# Steering_Converter_OG.net
KiCad netlist of a schematic drawn in Altium Designer
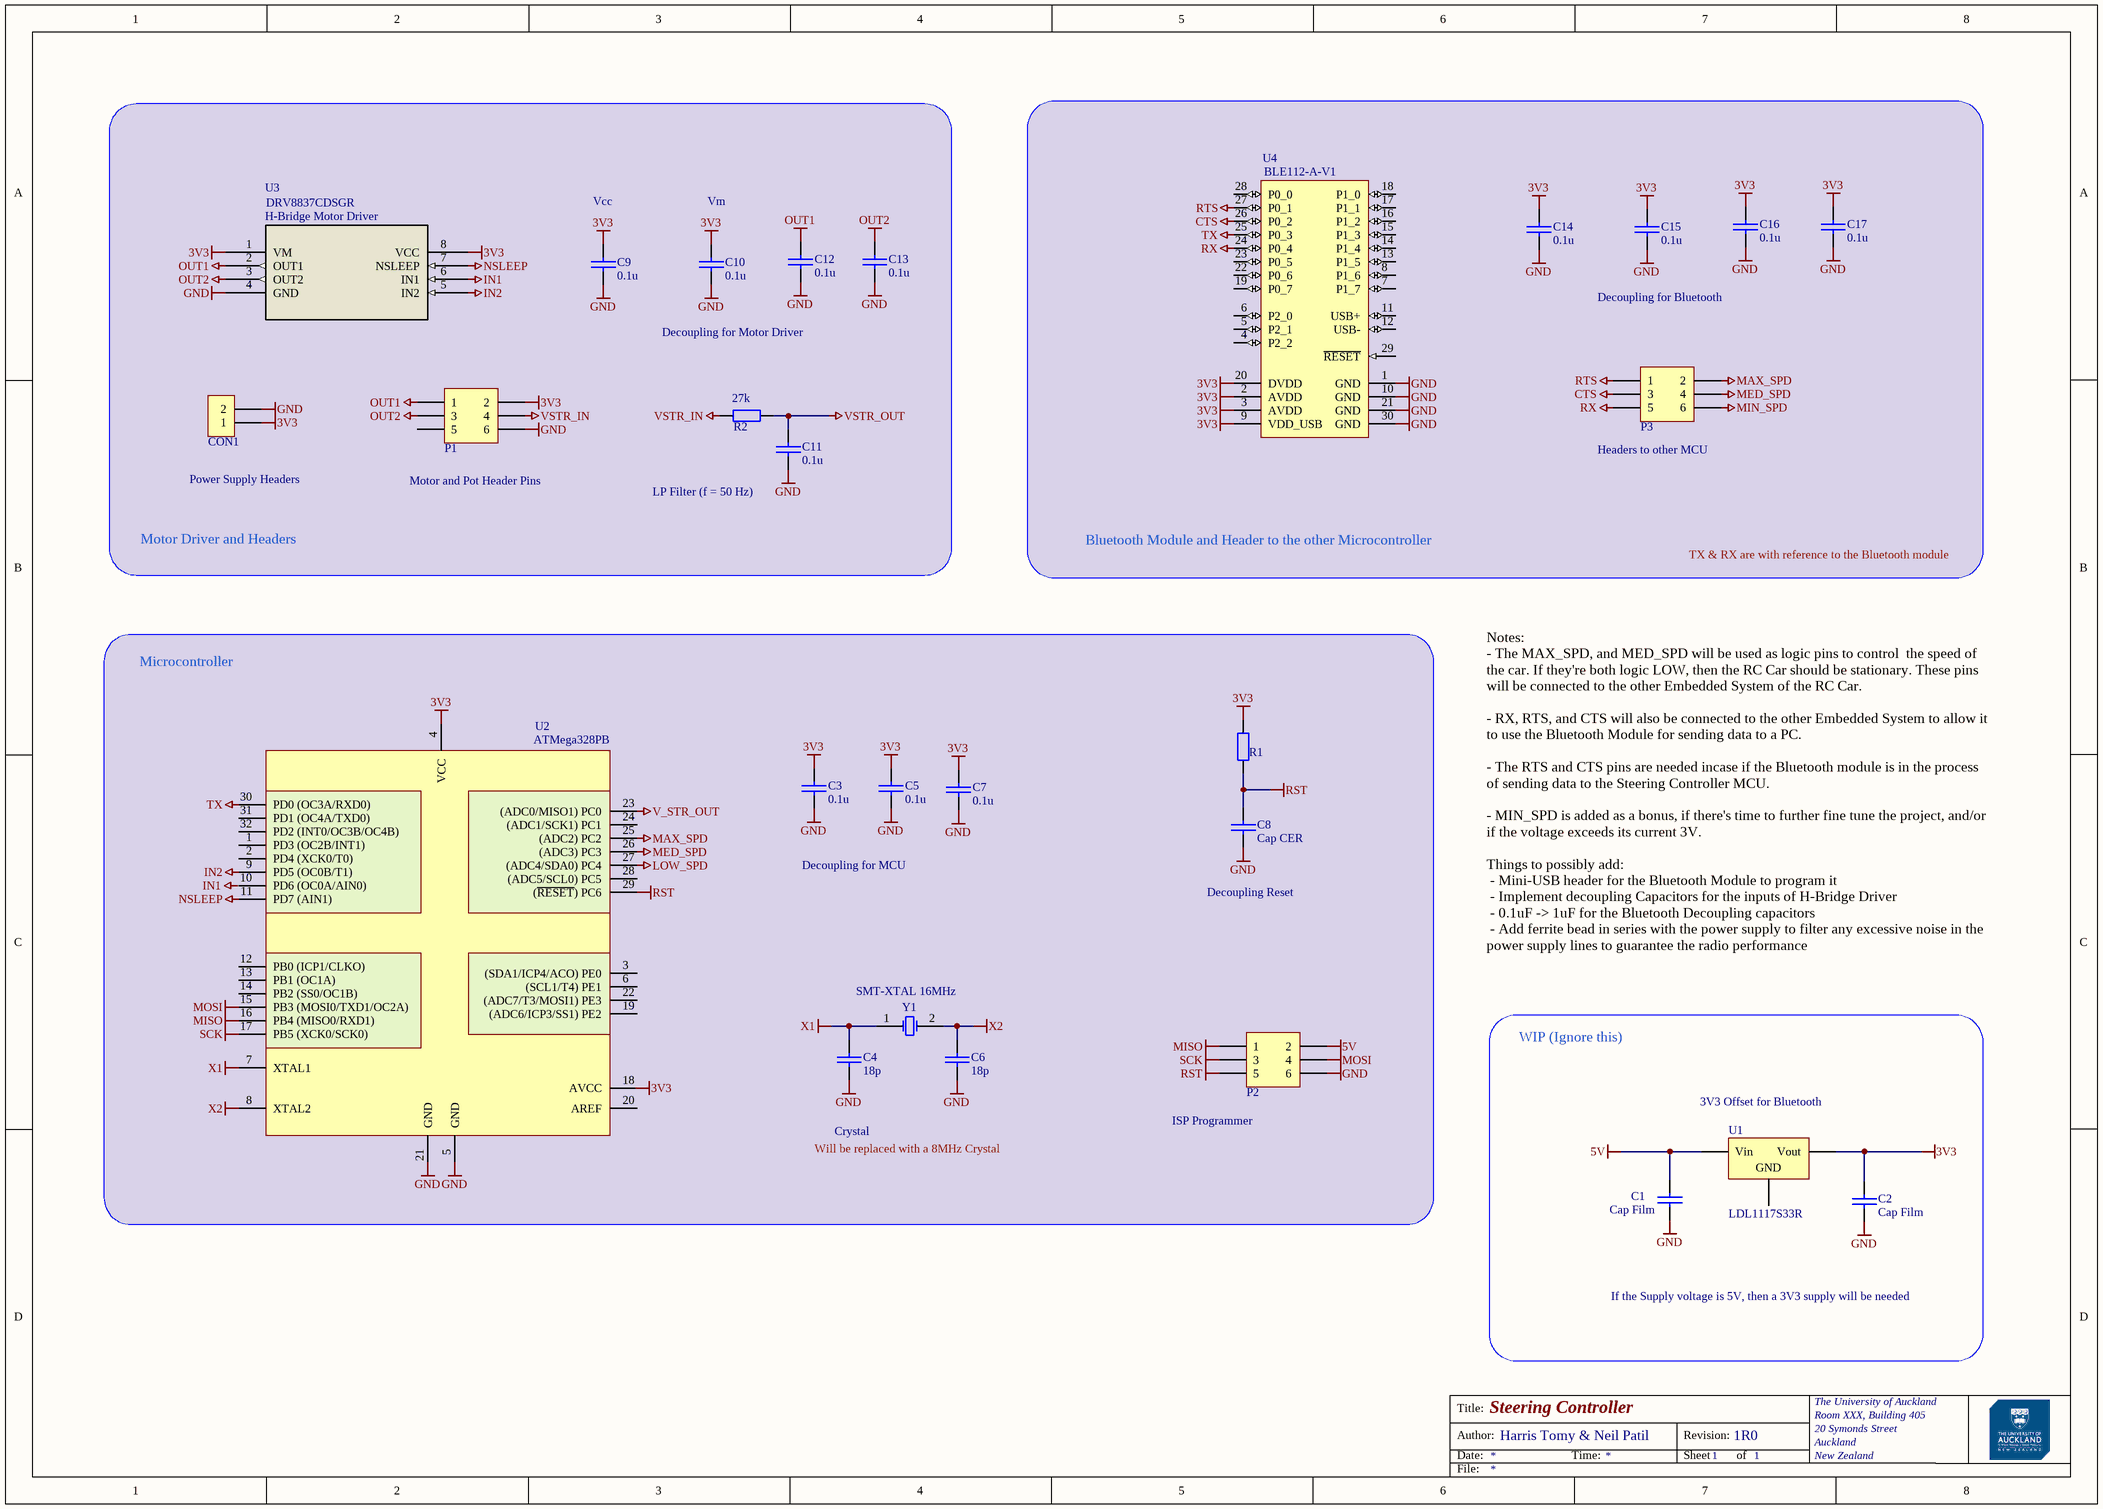
[diagram p0: Steering_Converter_OG.SchDoc]

(export (version "E")
  (design (tool "Eeschema 10.0.6"))
  (components
    (comp (ref "C1")
      (value "Cap Film")
      (footprint "LDECE4150KA0N00")
      (description "CAP FILM 1.5UF 10% 50VDC 2824")
      (fields (field (name "MPN") "LDECE4150KA0N00") (field (name "MANUFACTURER") "KEMET"))
      (libsource (lib "E209_Lib") (part "Cap Film SMD LDECE4150KA0N00"))
    )
    (comp (ref "C2")
      (value "Cap Film")
      (footprint "LDECE4150KA0N00")
      (description "CAP FILM 1.5UF 10% 50VDC 2824")
      (fields (field (name "MPN") "LDECE4150KA0N00") (field (name "MANUFACTURER") "KEMET"))
      (libsource (lib "E209_Lib") (part "Cap Film SMD LDECE4150KA0N00"))
    )
    (comp (ref "C3")
      (value "0.1u")
      (footprint "C1206")
      (description "CAP CER 0.1UF 100V C0G 1206")
      (fields (field (name "MPN") "C3216C0G2A104J160AC") (field (name "MANUFACTURER") "TDK Corporation"))
      (libsource (lib "E209_Lib") (part "Cap CER Decoup C3216C0G2A104J160AC"))
    )
    (comp (ref "C4")
      (value "18p")
      (footprint "C1206")
      (description "CAP CER 0.1UF 100V C0G 1206")
      (fields (field (name "MPN") "C3216C0G2A104J160AC") (field (name "MANUFACTURER") "TDK Corporation"))
      (libsource (lib "E209_Lib") (part "Cap CER Decoup C3216C0G2A104J160AC"))
    )
    (comp (ref "C5")
      (value "0.1u")
      (footprint "C1206")
      (description "CAP CER 0.1UF 100V C0G 1206")
      (fields (field (name "MPN") "C3216C0G2A104J160AC") (field (name "MANUFACTURER") "TDK Corporation"))
      (libsource (lib "E209_Lib") (part "Cap CER Decoup C3216C0G2A104J160AC"))
    )
    (comp (ref "C6")
      (value "18p")
      (footprint "C1206")
      (description "CAP CER 0.1UF 100V C0G 1206")
      (fields (field (name "MPN") "C3216C0G2A104J160AC") (field (name "MANUFACTURER") "TDK Corporation"))
      (libsource (lib "E209_Lib") (part "Cap CER Decoup C3216C0G2A104J160AC"))
    )
    (comp (ref "C7")
      (value "0.1u")
      (footprint "C1206")
      (description "CAP CER 0.1UF 100V C0G 1206")
      (fields (field (name "MPN") "C3216C0G2A104J160AC") (field (name "MANUFACTURER") "TDK Corporation"))
      (libsource (lib "E209_Lib") (part "Cap CER Decoup C3216C0G2A104J160AC"))
    )
    (comp (ref "C8")
      (value "Cap CER")
      (footprint "C1206")
      (description "CAP CER 0.1UF 100V C0G 1206")
      (fields (field (name "MPN") "C3216C0G2A104J160AC") (field (name "MANUFACTURER") "TDK Corporation"))
      (libsource (lib "E209_Lib") (part "Cap CER Decoup C3216C0G2A104J160AC"))
    )
    (comp (ref "C9")
      (value "0.1u")
      (footprint "C1206")
      (description "CAP CER 0.1UF 100V C0G 1206")
      (fields (field (name "MPN") "C3216C0G2A104J160AC") (field (name "MANUFACTURER") "TDK Corporation"))
      (libsource (lib "E209_Lib") (part "Cap CER Decoup C3216C0G2A104J160AC"))
    )
    (comp (ref "C10")
      (value "0.1u")
      (footprint "C1206")
      (description "CAP CER 0.1UF 100V C0G 1206")
      (fields (field (name "MPN") "C3216C0G2A104J160AC") (field (name "MANUFACTURER") "TDK Corporation"))
      (libsource (lib "E209_Lib") (part "Cap CER Decoup C3216C0G2A104J160AC"))
    )
    (comp (ref "C11")
      (value "0.1u")
      (footprint "C1206")
      (description "CAP CER 0.1UF 100V C0G 1206")
      (fields (field (name "MPN") "C3216C0G2A104J160AC") (field (name "MANUFACTURER") "TDK Corporation"))
      (libsource (lib "E209_Lib") (part "Cap CER Decoup C3216C0G2A104J160AC"))
    )
    (comp (ref "C12")
      (value "0.1u")
      (footprint "C1206")
      (description "CAP CER 0.1UF 100V C0G 1206")
      (fields (field (name "MPN") "C3216C0G2A104J160AC") (field (name "MANUFACTURER") "TDK Corporation"))
      (libsource (lib "E209_Lib") (part "Cap CER Decoup C3216C0G2A104J160AC"))
    )
    (comp (ref "C13")
      (value "0.1u")
      (footprint "C1206")
      (description "CAP CER 0.1UF 100V C0G 1206")
      (fields (field (name "MPN") "C3216C0G2A104J160AC") (field (name "MANUFACTURER") "TDK Corporation"))
      (libsource (lib "E209_Lib") (part "Cap CER Decoup C3216C0G2A104J160AC"))
    )
    (comp (ref "C14")
      (value "0.1u")
      (footprint "C1206")
      (description "CAP CER 0.1UF 100V C0G 1206")
      (fields (field (name "MPN") "C3216C0G2A104J160AC") (field (name "MANUFACTURER") "TDK Corporation"))
      (libsource (lib "E209_Lib") (part "Cap CER Decoup C3216C0G2A104J160AC"))
    )
    (comp (ref "C15")
      (value "0.1u")
      (footprint "C1206")
      (description "CAP CER 0.1UF 100V C0G 1206")
      (fields (field (name "MPN") "C3216C0G2A104J160AC") (field (name "MANUFACTURER") "TDK Corporation"))
      (libsource (lib "E209_Lib") (part "Cap CER Decoup C3216C0G2A104J160AC"))
    )
    (comp (ref "C16")
      (value "0.1u")
      (footprint "C1206")
      (description "CAP CER 0.1UF 100V C0G 1206")
      (fields (field (name "MPN") "C3216C0G2A104J160AC") (field (name "MANUFACTURER") "TDK Corporation"))
      (libsource (lib "E209_Lib") (part "Cap CER Decoup C3216C0G2A104J160AC"))
    )
    (comp (ref "C17")
      (value "0.1u")
      (footprint "C1206")
      (description "CAP CER 0.1UF 100V C0G 1206")
      (fields (field (name "MPN") "C3216C0G2A104J160AC") (field (name "MANUFACTURER") "TDK Corporation"))
      (libsource (lib "E209_Lib") (part "Cap CER Decoup C3216C0G2A104J160AC"))
    )
    (comp (ref "CON1")
      (value "Header 2X1")
      (footprint "HDR2X1_2P54")
      (libsource (lib "CommonDevices_V1") (part "HDR2X1"))
    )
    (comp (ref "P1")
      (value "HDR3X2")
      (footprint "HDR2X3_2P54")
      (description "Header, 3-Pin, Dual row")
      (libsource (lib "CommonDevices_V1") (part "HDR3X2"))
    )
    (comp (ref "P2")
      (value "HDR3X2")
      (footprint "HDR2X3_2P54")
      (description "Header, 3-Pin, Dual row")
      (libsource (lib "CommonDevices_V1") (part "HDR3X2"))
    )
    (comp (ref "P3")
      (value "HDR3X2")
      (footprint "HDR2X3_2P54")
      (description "Header, 3-Pin, Dual row")
      (libsource (lib "CommonDevices_V1") (part "HDR3X2"))
    )
    (comp (ref "R1")
      (value "Resistor 1206")
      (footprint "R1206")
      (description "RES1206")
      (fields (field (name "MPN") "?"))
      (libsource (lib "E209_Lib") (part "RES1206"))
    )
    (comp (ref "R2")
      (value "Resistor 0805")
      (footprint "R0805")
      (description "RES0805")
      (fields (field (name "MPN") "?"))
      (libsource (lib "E209_Lib") (part "RES0805"))
    )
    (comp (ref "U1")
      (value "LDL1117S33R")
      (footprint "SOT223L")
      (description "IC REG LINEAR 3.3V 1.2A SOT223")
      (fields (field (name "MANUFACTURER") "STMicroelectronics"))
      (libsource (lib "E209_Lib") (part "LDO LDL1117S33R"))
    )
    (comp (ref "U2")
      (value "ATMega328PB")
      (footprint "TQFP32")
      (description "IC MCU 8BIT 32KB FLASH 32TQFP")
      (libsource (lib "CommonDevices_V1") (part "ATMega328PB"))
    )
    (comp (ref "U3")
      (value "DRV8837CDSGR")
      (footprint "DSG8_P9X1P6_TEX")
      (description "No Description Available")
      (fields (field (name "COPYRIGHT") "Copyright (C) 2018 Accelerated Designs. All rights reserved"))
      (libsource (lib "H-Bridge_Driver_DRV8837C") (part "DRV8837CDSGR"))
    )
    (comp (ref "U4")
      (value "BLE112-A-V1")
      (footprint "BLUE-BLE112-A-V1_V")
      (libsource (lib "Integrated_Library1") (part "BLE112-A-V1"))
    )
    (comp (ref "Y1")
      (value "SMT-XTAL 16MHz")
      (footprint "HC49-US")
      (description "9C-16.000MAAJ-T crystal 16.0000MHZ 18PF SMD")
      (fields
        (field (name "MANUFACTURER") "TXC CORPORATION")
        (field (name "MANUFACTURER PART NUMBER") "9C-16.000MAAJ-T")
      )
      (libsource (lib "EE209_Library") (part "TXC9C-16_XTAL_SMT"))
    )
  )
  (nets
    (net (code "1") (name "3V3") (class "Default")
      (node (ref "C10") (pin "2") (pinfunction "2_2") (pintype "passive"))
      (node (ref "C14") (pin "2") (pinfunction "2_2") (pintype "passive"))
      (node (ref "C15") (pin "2") (pinfunction "2_2") (pintype "passive"))
      (node (ref "C16") (pin "2") (pinfunction "2_2") (pintype "passive"))
      (node (ref "C17") (pin "2") (pinfunction "2_2") (pintype "passive"))
      (node (ref "C2") (pin "2") (pinfunction "2_2") (pintype "passive"))
      (node (ref "C3") (pin "2") (pinfunction "2_2") (pintype "passive"))
      (node (ref "C5") (pin "2") (pinfunction "2_2") (pintype "passive"))
      (node (ref "C7") (pin "2") (pinfunction "2_2") (pintype "passive"))
      (node (ref "C9") (pin "2") (pinfunction "2_2") (pintype "passive"))
      (node (ref "CON1") (pin "1") (pinfunction "1_1") (pintype "passive"))
      (node (ref "P1") (pin "2") (pinfunction "2_2") (pintype "passive"))
      (node (ref "R1") (pin "1") (pinfunction "1_1") (pintype "passive"))
      (node (ref "U1") (pin "2") (pinfunction "Vout_2") (pintype "passive"))
      (node (ref "U2") (pin "4") (pinfunction "VCC_4") (pintype "passive"))
      (node (ref "U3") (pin "1") (pinfunction "VM_1") (pintype "power_in"))
      (node (ref "U3") (pin "8") (pinfunction "VCC_8") (pintype "power_in"))
      (node (ref "U4") (pin "2") (pinfunction "AVDD_2") (pintype "power_in"))
      (node (ref "U4") (pin "20") (pinfunction "DVDD_20") (pintype "power_in"))
      (node (ref "U4") (pin "3") (pinfunction "AVDD_3") (pintype "power_in"))
      (node (ref "U4") (pin "9") (pinfunction "VDD_USB_9") (pintype "power_in"))
    )
    (net (code "2") (name "5V") (class "Default")
      (node (ref "C1") (pin "2") (pinfunction "2_2") (pintype "passive"))
      (node (ref "P2") (pin "2") (pinfunction "2_2") (pintype "passive"))
      (node (ref "U1") (pin "3") (pinfunction "Vin_3") (pintype "passive"))
    )
    (net (code "3") (name "CTS") (class "Default")
      (node (ref "P3") (pin "3") (pinfunction "3_3") (pintype "passive"))
      (node (ref "U4") (pin "26") (pinfunction "P0_2_26") (pintype "bidirectional"))
    )
    (net (code "4") (name "GND") (class "Default")
      (node (ref "C1") (pin "1") (pinfunction "1_1") (pintype "passive"))
      (node (ref "C10") (pin "1") (pinfunction "1_1") (pintype "passive"))
      (node (ref "C11") (pin "1") (pinfunction "1_1") (pintype "passive"))
      (node (ref "C12") (pin "1") (pinfunction "1_1") (pintype "passive"))
      (node (ref "C13") (pin "1") (pinfunction "1_1") (pintype "passive"))
      (node (ref "C14") (pin "1") (pinfunction "1_1") (pintype "passive"))
      (node (ref "C15") (pin "1") (pinfunction "1_1") (pintype "passive"))
      (node (ref "C16") (pin "1") (pinfunction "1_1") (pintype "passive"))
      (node (ref "C17") (pin "1") (pinfunction "1_1") (pintype "passive"))
      (node (ref "C2") (pin "1") (pinfunction "1_1") (pintype "passive"))
      (node (ref "C3") (pin "1") (pinfunction "1_1") (pintype "passive"))
      (node (ref "C4") (pin "1") (pinfunction "1_1") (pintype "passive"))
      (node (ref "C5") (pin "1") (pinfunction "1_1") (pintype "passive"))
      (node (ref "C6") (pin "1") (pinfunction "1_1") (pintype "passive"))
      (node (ref "C7") (pin "1") (pinfunction "1_1") (pintype "passive"))
      (node (ref "C8") (pin "1") (pinfunction "1_1") (pintype "passive"))
      (node (ref "C9") (pin "1") (pinfunction "1_1") (pintype "passive"))
      (node (ref "CON1") (pin "2") (pinfunction "2_2") (pintype "passive"))
      (node (ref "P1") (pin "6") (pinfunction "6_6") (pintype "passive"))
      (node (ref "P2") (pin "6") (pinfunction "6_6") (pintype "passive"))
      (node (ref "U2") (pin "21") (pinfunction "GND_21") (pintype "passive"))
      (node (ref "U2") (pin "5") (pinfunction "GND_5") (pintype "passive"))
      (node (ref "U3") (pin "4") (pinfunction "GND_4") (pintype "power_in"))
      (node (ref "U4") (pin "1") (pinfunction "GND_1") (pintype "power_in"))
      (node (ref "U4") (pin "10") (pinfunction "GND_10") (pintype "power_in"))
      (node (ref "U4") (pin "21") (pinfunction "GND_21") (pintype "power_in"))
      (node (ref "U4") (pin "30") (pinfunction "GND_30") (pintype "power_in"))
    )
    (net (code "5") (name "IN1") (class "Default")
      (node (ref "U3") (pin "6") (pinfunction "IN1_6") (pintype "input"))
    )
    (net (code "6") (name "IN2") (class "Default")
      (node (ref "U2") (pin "9") (pinfunction "PD5_(OC0B/T1)_9") (pintype "passive"))
      (node (ref "U3") (pin "5") (pinfunction "IN2_5") (pintype "input"))
    )
    (net (code "7") (name "LOW_SPD") (class "Default")
      (node (ref "U2") (pin "27") (pinfunction "(ADC4/SDA0)_PC4_27") (pintype "passive"))
    )
    (net (code "8") (name "MAX_SPD") (class "Default")
      (node (ref "P3") (pin "2") (pinfunction "2_2") (pintype "passive"))
      (node (ref "U2") (pin "25") (pinfunction "(ADC2)_PC2_25") (pintype "passive"))
    )
    (net (code "9") (name "MED_SPD") (class "Default")
      (node (ref "P3") (pin "4") (pinfunction "4_4") (pintype "passive"))
      (node (ref "U2") (pin "26") (pinfunction "(ADC3)_PC3_26") (pintype "passive"))
    )
    (net (code "10") (name "MIN_SPD") (class "Default")
      (node (ref "P3") (pin "6") (pinfunction "6_6") (pintype "passive"))
    )
    (net (code "11") (name "MISO") (class "Default")
      (node (ref "P2") (pin "1") (pinfunction "1_1") (pintype "passive"))
      (node (ref "U2") (pin "16") (pinfunction "PB4_(MISO0/RXD1)_16") (pintype "passive"))
    )
    (net (code "12") (name "MOSI") (class "Default")
      (node (ref "P2") (pin "4") (pinfunction "4_4") (pintype "passive"))
      (node (ref "U2") (pin "15") (pinfunction "PB3_(MOSI0/TXD1/OC2A)_15") (pintype "passive"))
    )
    (net (code "13") (name "NSLEEP") (class "Default")
      (node (ref "U2") (pin "11") (pinfunction "PD7_(AIN1)_11") (pintype "passive"))
      (node (ref "U3") (pin "7") (pinfunction "NSLEEP_7") (pintype "input"))
    )
    (net (code "14") (name "OUT1") (class "Default")
      (node (ref "C12") (pin "2") (pinfunction "2_2") (pintype "passive"))
      (node (ref "P1") (pin "1") (pinfunction "1_1") (pintype "passive"))
      (node (ref "U3") (pin "2") (pinfunction "OUT1_2") (pintype "output"))
    )
    (net (code "15") (name "OUT2") (class "Default")
      (node (ref "C13") (pin "2") (pinfunction "2_2") (pintype "passive"))
      (node (ref "P1") (pin "3") (pinfunction "3_3") (pintype "passive"))
      (node (ref "U3") (pin "3") (pinfunction "OUT2_3") (pintype "output"))
    )
    (net (code "16") (name "RST") (class "Default")
      (node (ref "C8") (pin "2") (pinfunction "2_2") (pintype "passive"))
      (node (ref "P2") (pin "5") (pinfunction "5_5") (pintype "passive"))
      (node (ref "R1") (pin "2") (pinfunction "2_2") (pintype "passive"))
      (node (ref "U2") (pin "29") (pinfunction "(~{RESET})_PC6_29") (pintype "passive"))
    )
    (net (code "17") (name "RTS") (class "Default")
      (node (ref "P3") (pin "1") (pinfunction "1_1") (pintype "passive"))
      (node (ref "U4") (pin "27") (pinfunction "P0_1_27") (pintype "bidirectional"))
    )
    (net (code "18") (name "RX") (class "Default")
      (node (ref "P3") (pin "5") (pinfunction "5_5") (pintype "passive"))
      (node (ref "U4") (pin "24") (pinfunction "P0_4_24") (pintype "bidirectional"))
    )
    (net (code "19") (name "SCK") (class "Default")
      (node (ref "P2") (pin "3") (pinfunction "3_3") (pintype "passive"))
      (node (ref "U2") (pin "17") (pinfunction "PB5_(XCK0/SCK0)_17") (pintype "passive"))
    )
    (net (code "20") (name "TX") (class "Default")
      (node (ref "U2") (pin "30") (pinfunction "PD0_(OC3A/RXD0)_30") (pintype "passive"))
      (node (ref "U4") (pin "25") (pinfunction "P0_3_25") (pintype "bidirectional"))
    )
    (net (code "21") (name "VSTR_IN") (class "Default")
      (node (ref "P1") (pin "4") (pinfunction "4_4") (pintype "passive"))
      (node (ref "R2") (pin "1") (pinfunction "1_1") (pintype "passive"))
    )
    (net (code "22") (name "VSTR_OUT") (class "Default")
      (node (ref "C11") (pin "2") (pinfunction "2_2") (pintype "passive"))
      (node (ref "R2") (pin "2") (pinfunction "2_2") (pintype "passive"))
    )
    (net (code "23") (name "V_STR_OUT") (class "Default")
      (node (ref "U2") (pin "23") (pinfunction "(ADC0/MISO1)_PC0_23") (pintype "passive"))
    )
    (net (code "24") (name "X1") (class "Default")
      (node (ref "C4") (pin "2") (pinfunction "2_2") (pintype "passive"))
      (node (ref "U2") (pin "7") (pinfunction "XTAL1_7") (pintype "passive"))
      (node (ref "Y1") (pin "1") (pinfunction "OSC1_1") (pintype "passive"))
    )
    (net (code "25") (name "X2") (class "Default")
      (node (ref "C6") (pin "2") (pinfunction "2_2") (pintype "passive"))
      (node (ref "U2") (pin "8") (pinfunction "XTAL2_8") (pintype "passive"))
      (node (ref "Y1") (pin "2") (pinfunction "OSC2_2") (pintype "passive"))
    )
    (net (code "26") (name "unconnected-(P1-Pad5)") (class "Default")
      (node (ref "P1") (pin "5") (pinfunction "5_5") (pintype "passive"))
    )
    (net (code "27") (name "unconnected-(U1-GND-Pad1)") (class "Default")
      (node (ref "U1") (pin "1") (pinfunction "GND_1") (pintype "passive"))
    )
    (net (code "28") (name "unconnected-(U2-(ADC1{slash}SCK1)_PC1-Pad24)") (class "Default")
      (node (ref "U2") (pin "24") (pinfunction "(ADC1/SCK1)_PC1_24") (pintype "passive"))
    )
    (net (code "29") (name "unconnected-(U2-(ADC5{slash}SCL0)_PC5-Pad28)") (class "Default")
      (node (ref "U2") (pin "28") (pinfunction "(ADC5/SCL0)_PC5_28") (pintype "passive"))
    )
    (net (code "30") (name "unconnected-(U2-(ADC6{slash}ICP3{slash}SS1)_PE2-Pad19)") (class "Default")
      (node (ref "U2") (pin "19") (pinfunction "(ADC6/ICP3/SS1)_PE2_19") (pintype "passive"))
    )
    (net (code "31") (name "unconnected-(U2-(ADC7{slash}T3{slash}MOSI1)_PE3-Pad22)") (class "Default")
      (node (ref "U2") (pin "22") (pinfunction "(ADC7/T3/MOSI1)_PE3_22") (pintype "passive"))
    )
    (net (code "32") (name "unconnected-(U2-(SCL1{slash}T4)_PE1-Pad6)") (class "Default")
      (node (ref "U2") (pin "6") (pinfunction "(SCL1/T4)_PE1_6") (pintype "passive"))
    )
    (net (code "33") (name "unconnected-(U2-(SDA1{slash}ICP4{slash}ACO)_PE0-Pad3)") (class "Default")
      (node (ref "U2") (pin "3") (pinfunction "(SDA1/ICP4/ACO)_PE0_3") (pintype "passive"))
    )
    (net (code "34") (name "unconnected-(U2-AREF-Pad20)") (class "Default")
      (node (ref "U2") (pin "20") (pinfunction "AREF_20") (pintype "passive"))
    )
    (net (code "35") (name "unconnected-(U2-AVCC-Pad18)") (class "Default")
      (node (ref "U2") (pin "18") (pinfunction "AVCC_18") (pintype "passive"))
    )
    (net (code "36") (name "unconnected-(U2-PB0_(ICP1{slash}CLKO)-Pad12)") (class "Default")
      (node (ref "U2") (pin "12") (pinfunction "PB0_(ICP1/CLKO)_12") (pintype "passive"))
    )
    (net (code "37") (name "unconnected-(U2-PB1_(OC1A)-Pad13)") (class "Default")
      (node (ref "U2") (pin "13") (pinfunction "PB1_(OC1A)_13") (pintype "passive"))
    )
    (net (code "38") (name "unconnected-(U2-PB2_(SS0{slash}OC1B)-Pad14)") (class "Default")
      (node (ref "U2") (pin "14") (pinfunction "PB2_(SS0/OC1B)_14") (pintype "passive"))
    )
    (net (code "39") (name "unconnected-(U2-PD1_(OC4A{slash}TXD0)-Pad31)") (class "Default")
      (node (ref "U2") (pin "31") (pinfunction "PD1_(OC4A/TXD0)_31") (pintype "passive"))
    )
    (net (code "40") (name "unconnected-(U2-PD2_(INT0{slash}OC3B{slash}OC4B)-Pad32)") (class "Default")
      (node (ref "U2") (pin "32") (pinfunction "PD2_(INT0/OC3B/OC4B)_32") (pintype "passive"))
    )
    (net (code "41") (name "unconnected-(U2-PD3_(OC2B{slash}INT1)-Pad1)") (class "Default")
      (node (ref "U2") (pin "1") (pinfunction "PD3_(OC2B/INT1)_1") (pintype "passive"))
    )
    (net (code "42") (name "unconnected-(U2-PD4_(XCK0{slash}T0)-Pad2)") (class "Default")
      (node (ref "U2") (pin "2") (pinfunction "PD4_(XCK0/T0)_2") (pintype "passive"))
    )
    (net (code "43") (name "unconnected-(U2-PD6_(OC0A{slash}AIN0)-Pad10)") (class "Default")
      (node (ref "U2") (pin "10") (pinfunction "PD6_(OC0A/AIN0)_10") (pintype "passive"))
    )
    (net (code "44") (name "unconnected-(U4-P0_0-Pad28)") (class "Default")
      (node (ref "U4") (pin "28") (pinfunction "P0_0_28") (pintype "bidirectional"))
    )
    (net (code "45") (name "unconnected-(U4-P0_5-Pad23)") (class "Default")
      (node (ref "U4") (pin "23") (pinfunction "P0_5_23") (pintype "bidirectional"))
    )
    (net (code "46") (name "unconnected-(U4-P0_6-Pad22)") (class "Default")
      (node (ref "U4") (pin "22") (pinfunction "P0_6_22") (pintype "bidirectional"))
    )
    (net (code "47") (name "unconnected-(U4-P0_7-Pad19)") (class "Default")
      (node (ref "U4") (pin "19") (pinfunction "P0_7_19") (pintype "bidirectional"))
    )
    (net (code "48") (name "unconnected-(U4-P1_0-Pad18)") (class "Default")
      (node (ref "U4") (pin "18") (pinfunction "P1_0_18") (pintype "bidirectional"))
    )
    (net (code "49") (name "unconnected-(U4-P1_1-Pad17)") (class "Default")
      (node (ref "U4") (pin "17") (pinfunction "P1_1_17") (pintype "bidirectional"))
    )
    (net (code "50") (name "unconnected-(U4-P1_2-Pad16)") (class "Default")
      (node (ref "U4") (pin "16") (pinfunction "P1_2_16") (pintype "bidirectional"))
    )
    (net (code "51") (name "unconnected-(U4-P1_3-Pad15)") (class "Default")
      (node (ref "U4") (pin "15") (pinfunction "P1_3_15") (pintype "bidirectional"))
    )
    (net (code "52") (name "unconnected-(U4-P1_4-Pad14)") (class "Default")
      (node (ref "U4") (pin "14") (pinfunction "P1_4_14") (pintype "bidirectional"))
    )
    (net (code "53") (name "unconnected-(U4-P1_5-Pad13)") (class "Default")
      (node (ref "U4") (pin "13") (pinfunction "P1_5_13") (pintype "bidirectional"))
    )
    (net (code "54") (name "unconnected-(U4-P1_6-Pad8)") (class "Default")
      (node (ref "U4") (pin "8") (pinfunction "P1_6_8") (pintype "bidirectional"))
    )
    (net (code "55") (name "unconnected-(U4-P1_7-Pad7)") (class "Default")
      (node (ref "U4") (pin "7") (pinfunction "P1_7_7") (pintype "bidirectional"))
    )
    (net (code "56") (name "unconnected-(U4-P2_0-Pad6)") (class "Default")
      (node (ref "U4") (pin "6") (pinfunction "P2_0_6") (pintype "bidirectional"))
    )
    (net (code "57") (name "unconnected-(U4-P2_1-Pad5)") (class "Default")
      (node (ref "U4") (pin "5") (pinfunction "P2_1_5") (pintype "bidirectional"))
    )
    (net (code "58") (name "unconnected-(U4-P2_2-Pad4)") (class "Default")
      (node (ref "U4") (pin "4") (pinfunction "P2_2_4") (pintype "bidirectional"))
    )
    (net (code "59") (name "unconnected-(U4-USB+-Pad11)") (class "Default")
      (node (ref "U4") (pin "11") (pinfunction "USB+_11") (pintype "bidirectional"))
    )
    (net (code "60") (name "unconnected-(U4-USB--Pad12)") (class "Default")
      (node (ref "U4") (pin "12") (pinfunction "USB-_12") (pintype "bidirectional"))
    )
    (net (code "61") (name "unconnected-(U4-~{RESET}-Pad29)") (class "Default")
      (node (ref "U4") (pin "29") (pinfunction "~{RESET}_29") (pintype "input"))
    )
  )
)
